# AccShelf.net
KiCad netlist of a schematic drawn in Altium Designer
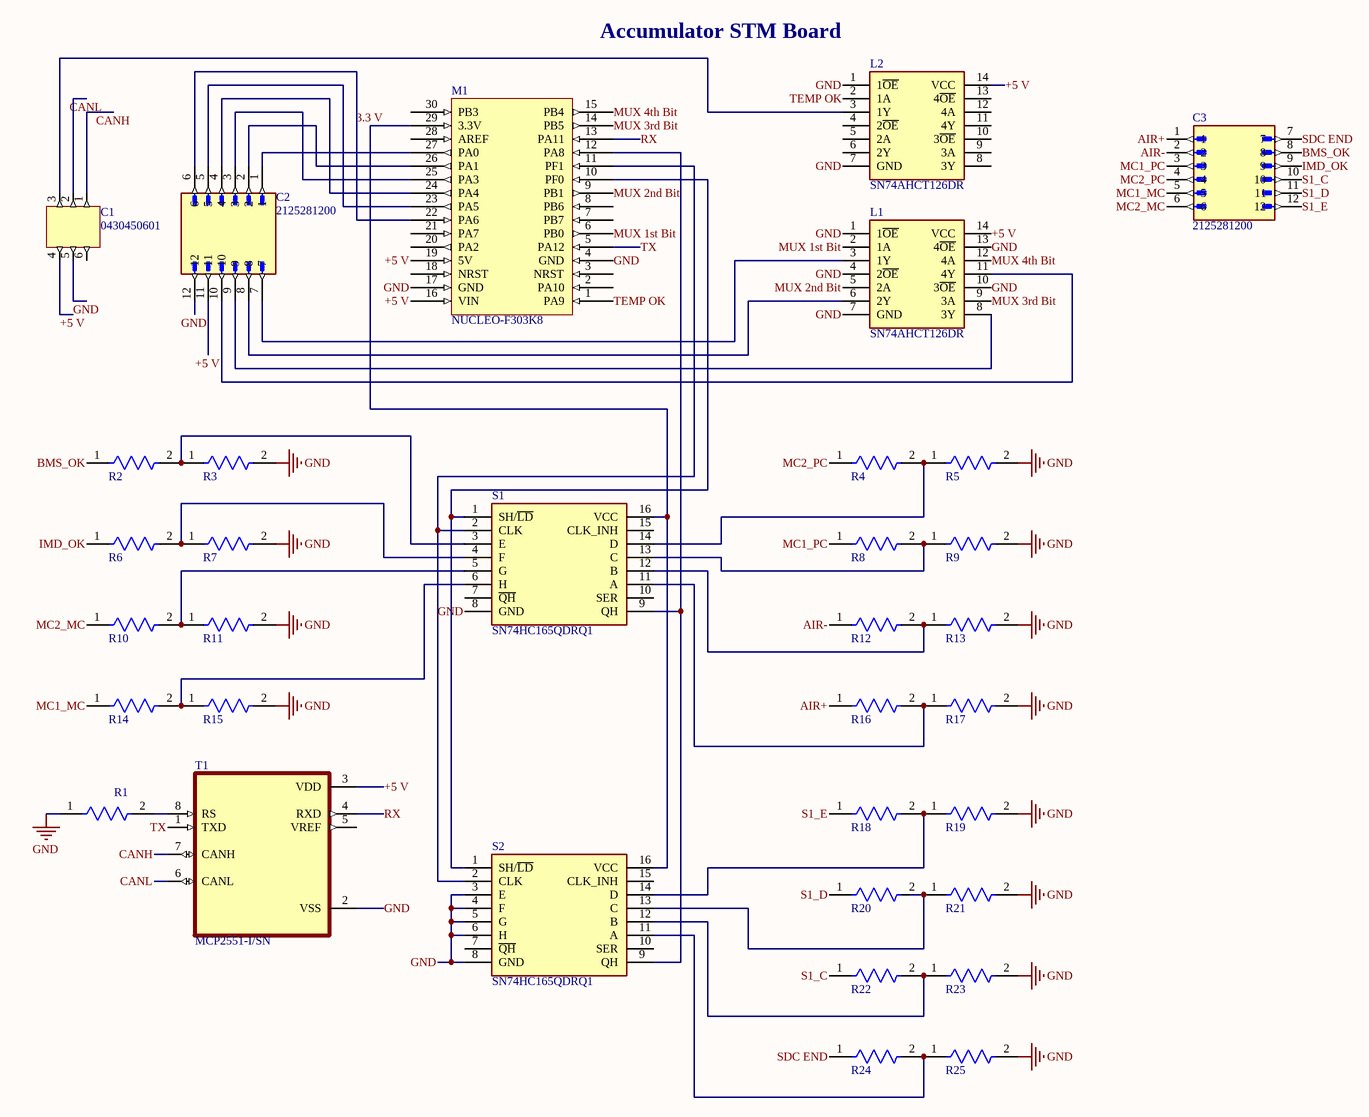
[diagram p0: AccShelf.SchDoc]

(export (version "E")
  (design (tool "Eeschema 10.0.6"))
  (components
    (comp (ref "C1")
      (value "0430450601")
      (footprint "6 Pin Dual Connector")
      (description "Rectangular Power Connector, 6 Contact(s), Male, Solder Terminal, Receptacle")
      (fields
        (field (name "MANUFACTURER") "Sullins")
        (field (name "MANUFACTURER PART NUMBER") "PPPC032LJBN-RC")
      )
      (libsource (lib "AccShelf") (part "0430450601"))
    )
    (comp (ref "C2")
      (value "2125281200")
      (footprint "12 Pin Dual Inline Connector")
      (description "Conn Micro-Fit Power HDR 12 POS 3mm Solder RA Through Hole 12 Terminal Single Port Tray")
      (fields (field (name "MF") "{'manufacturer': u'Molex'}") (field (name "MANUFACTURER") "Molex"))
      (libsource (lib "AccShelf") (part "2125281200"))
    )
    (comp (ref "C3")
      (value "2125281200")
      (footprint "12 Pin Dual Inline Connector")
      (description "Conn Micro-Fit Power HDR 12 POS 3mm Solder RA Through Hole 12 Terminal Single Port Tray")
      (fields (field (name "MF") "{'manufacturer': u'Molex'}") (field (name "MANUFACTURER") "Molex"))
      (libsource (lib "") (part "2125281200_1"))
    )
    (comp (ref "L1")
      (value "SN74AHCT126DR")
      (footprint "Level Shifter")
      (description "Bus Driver, AHCT/VHCT/VT Series, 4-Func, 1-Bit, True Output, CMOS, PDSO14")
      (fields
        (field (name "MANUFACTURER_PART_NUMBER") "74AHCT125S14-13")
        (field (name "MOUSER PART NUMBER") "621-74AHCT125S14-13")
      )
      (libsource (lib "AccShelf") (part "SN74AHCT126DR"))
    )
    (comp (ref "L2")
      (value "SN74AHCT126DR")
      (footprint "Level Shifter")
      (description "Bus Driver, AHCT/VHCT/VT Series, 4-Func, 1-Bit, True Output, CMOS, PDSO14")
      (fields
        (field (name "MANUFACTURER_PART_NUMBER") "74AHCT125S14-13")
        (field (name "MOUSER PART NUMBER") "621-74AHCT125S14-13")
      )
      (libsource (lib "AccShelf") (part "SN74AHCT126DR"))
    )
    (comp (ref "M1")
      (value "NUCLEO-F303K8")
      (footprint "STM Footprint")
      (description "Boards/Accessories")
      (fields (field (name "MANUFACTURER") "STMicroelectronics"))
      (libsource (lib "AccShelf") (part "NUCLEO-F303K8"))
    )
    (comp (ref "R1")
      (value "CRCW080510K0FKEA")
      (footprint "FP-CRCW0805-e3-IPC_A")
      (description "RES Thick Film, 10kΩ, 1%, 0.125W, 100ppm/°C, 0805")
      (fields (field (name "TOLERANCE") "1%") (field (name "MANUFACTURER") "Vishay"))
      (libsource (lib "Altium Content Vault") (part "1029c3af85768c4190bb7ad29bc67b5"))
    )
    (comp (ref "R2")
      (value "CRCW0805270KFKEA")
      (footprint "FP-CRCW0805-e3-IPC_A")
      (description "RES Thick Film, 270kΩ, 1%, 0.125W, 100ppm/°C, 0805")
      (fields (field (name "TOLERANCE") "1%"))
      (libsource (lib "Altium Content Vault") (part "1029c3af85768c4190bb7ad29bc67b5"))
    )
    (comp (ref "R3")
      (value "CRCW0805100KFKEA")
      (footprint "FP-CRCW0805-e3-MFG")
      (description "RES Thick Film, 100kΩ, 1%, 0.125W, 100ppm/°C, 0805")
      (fields (field (name "TOLERANCE") "1%"))
      (libsource (lib "Altium Content Vault") (part "1029c3af85768c4190bb7ad29bc67b5"))
    )
    (comp (ref "R4")
      (value "CRCW0805270KFKEA")
      (footprint "FP-CRCW0805-e3-IPC_A")
      (description "RES Thick Film, 270kΩ, 1%, 0.125W, 100ppm/°C, 0805")
      (fields (field (name "TOLERANCE") "1%"))
      (libsource (lib "Altium Content Vault") (part "1029c3af85768c4190bb7ad29bc67b5"))
    )
    (comp (ref "R5")
      (value "CRCW0805100KFKEA")
      (footprint "FP-CRCW0805-e3-MFG")
      (description "RES Thick Film, 100kΩ, 1%, 0.125W, 100ppm/°C, 0805")
      (fields (field (name "TOLERANCE") "1%"))
      (libsource (lib "Altium Content Vault") (part "1029c3af85768c4190bb7ad29bc67b5"))
    )
    (comp (ref "R6")
      (value "CRCW0805270KFKEA")
      (footprint "FP-CRCW0805-e3-IPC_A")
      (description "RES Thick Film, 270kΩ, 1%, 0.125W, 100ppm/°C, 0805")
      (fields (field (name "TOLERANCE") "1%"))
      (libsource (lib "Altium Content Vault") (part "1029c3af85768c4190bb7ad29bc67b5"))
    )
    (comp (ref "R7")
      (value "CRCW0805100KFKEA")
      (footprint "FP-CRCW0805-e3-MFG")
      (description "RES Thick Film, 100kΩ, 1%, 0.125W, 100ppm/°C, 0805")
      (fields (field (name "TOLERANCE") "1%"))
      (libsource (lib "Altium Content Vault") (part "1029c3af85768c4190bb7ad29bc67b5"))
    )
    (comp (ref "R8")
      (value "CRCW0805270KFKEA")
      (footprint "FP-CRCW0805-e3-IPC_A")
      (description "RES Thick Film, 270kΩ, 1%, 0.125W, 100ppm/°C, 0805")
      (fields (field (name "TOLERANCE") "1%"))
      (libsource (lib "Altium Content Vault") (part "1029c3af85768c4190bb7ad29bc67b5"))
    )
    (comp (ref "R9")
      (value "CRCW0805100KFKEA")
      (footprint "FP-CRCW0805-e3-MFG")
      (description "RES Thick Film, 100kΩ, 1%, 0.125W, 100ppm/°C, 0805")
      (fields (field (name "TOLERANCE") "1%"))
      (libsource (lib "Altium Content Vault") (part "1029c3af85768c4190bb7ad29bc67b5"))
    )
    (comp (ref "R10")
      (value "CRCW0805270KFKEA")
      (footprint "FP-CRCW0805-e3-IPC_A")
      (description "RES Thick Film, 270kΩ, 1%, 0.125W, 100ppm/°C, 0805")
      (fields (field (name "TOLERANCE") "1%"))
      (libsource (lib "Altium Content Vault") (part "1029c3af85768c4190bb7ad29bc67b5"))
    )
    (comp (ref "R11")
      (value "CRCW0805100KFKEA")
      (footprint "FP-CRCW0805-e3-MFG")
      (description "RES Thick Film, 100kΩ, 1%, 0.125W, 100ppm/°C, 0805")
      (fields (field (name "TOLERANCE") "1%"))
      (libsource (lib "Altium Content Vault") (part "1029c3af85768c4190bb7ad29bc67b5"))
    )
    (comp (ref "R12")
      (value "CRCW0805270KFKEA")
      (footprint "FP-CRCW0805-e3-IPC_A")
      (description "RES Thick Film, 270kΩ, 1%, 0.125W, 100ppm/°C, 0805")
      (fields (field (name "TOLERANCE") "1%"))
      (libsource (lib "Altium Content Vault") (part "1029c3af85768c4190bb7ad29bc67b5"))
    )
    (comp (ref "R13")
      (value "CRCW0805100KFKEA")
      (footprint "FP-CRCW0805-e3-MFG")
      (description "RES Thick Film, 100kΩ, 1%, 0.125W, 100ppm/°C, 0805")
      (fields (field (name "TOLERANCE") "1%"))
      (libsource (lib "Altium Content Vault") (part "1029c3af85768c4190bb7ad29bc67b5"))
    )
    (comp (ref "R14")
      (value "CRCW0805270KFKEA")
      (footprint "FP-CRCW0805-e3-IPC_A")
      (description "RES Thick Film, 270kΩ, 1%, 0.125W, 100ppm/°C, 0805")
      (fields (field (name "TOLERANCE") "1%"))
      (libsource (lib "Altium Content Vault") (part "1029c3af85768c4190bb7ad29bc67b5"))
    )
    (comp (ref "R15")
      (value "CRCW0805100KFKEA")
      (footprint "FP-CRCW0805-e3-MFG")
      (description "RES Thick Film, 100kΩ, 1%, 0.125W, 100ppm/°C, 0805")
      (fields (field (name "TOLERANCE") "1%"))
      (libsource (lib "Altium Content Vault") (part "1029c3af85768c4190bb7ad29bc67b5"))
    )
    (comp (ref "R16")
      (value "CRCW0805270KFKEA")
      (footprint "FP-CRCW0805-e3-IPC_A")
      (description "RES Thick Film, 270kΩ, 1%, 0.125W, 100ppm/°C, 0805")
      (fields (field (name "TOLERANCE") "1%"))
      (libsource (lib "Altium Content Vault") (part "1029c3af85768c4190bb7ad29bc67b5"))
    )
    (comp (ref "R17")
      (value "CRCW0805100KFKEA")
      (footprint "FP-CRCW0805-e3-MFG")
      (description "RES Thick Film, 100kΩ, 1%, 0.125W, 100ppm/°C, 0805")
      (fields (field (name "TOLERANCE") "1%"))
      (libsource (lib "Altium Content Vault") (part "1029c3af85768c4190bb7ad29bc67b5"))
    )
    (comp (ref "R18")
      (value "CRCW0805270KFKEA")
      (footprint "FP-CRCW0805-e3-IPC_A")
      (description "RES Thick Film, 270kΩ, 1%, 0.125W, 100ppm/°C, 0805")
      (fields (field (name "TOLERANCE") "1%"))
      (libsource (lib "Altium Content Vault") (part "1029c3af85768c4190bb7ad29bc67b5"))
    )
    (comp (ref "R19")
      (value "CRCW0805100KFKEA")
      (footprint "FP-CRCW0805-e3-MFG")
      (description "RES Thick Film, 100kΩ, 1%, 0.125W, 100ppm/°C, 0805")
      (fields (field (name "TOLERANCE") "1%"))
      (libsource (lib "Altium Content Vault") (part "1029c3af85768c4190bb7ad29bc67b5"))
    )
    (comp (ref "R20")
      (value "CRCW0805270KFKEA")
      (footprint "FP-CRCW0805-e3-IPC_A")
      (description "RES Thick Film, 270kΩ, 1%, 0.125W, 100ppm/°C, 0805")
      (fields (field (name "TOLERANCE") "1%"))
      (libsource (lib "Altium Content Vault") (part "1029c3af85768c4190bb7ad29bc67b5"))
    )
    (comp (ref "R21")
      (value "CRCW0805100KFKEA")
      (footprint "FP-CRCW0805-e3-MFG")
      (description "RES Thick Film, 100kΩ, 1%, 0.125W, 100ppm/°C, 0805")
      (fields (field (name "TOLERANCE") "1%"))
      (libsource (lib "Altium Content Vault") (part "1029c3af85768c4190bb7ad29bc67b5"))
    )
    (comp (ref "R22")
      (value "CRCW0805270KFKEA")
      (footprint "FP-CRCW0805-e3-IPC_A")
      (description "RES Thick Film, 270kΩ, 1%, 0.125W, 100ppm/°C, 0805")
      (fields (field (name "TOLERANCE") "1%"))
      (libsource (lib "Altium Content Vault") (part "1029c3af85768c4190bb7ad29bc67b5"))
    )
    (comp (ref "R23")
      (value "CRCW0805100KFKEA")
      (footprint "FP-CRCW0805-e3-MFG")
      (description "RES Thick Film, 100kΩ, 1%, 0.125W, 100ppm/°C, 0805")
      (fields (field (name "TOLERANCE") "1%"))
      (libsource (lib "Altium Content Vault") (part "1029c3af85768c4190bb7ad29bc67b5"))
    )
    (comp (ref "R24")
      (value "CRCW0805270KFKEA")
      (footprint "FP-CRCW0805-e3-IPC_A")
      (description "RES Thick Film, 270kΩ, 1%, 0.125W, 100ppm/°C, 0805")
      (fields (field (name "TOLERANCE") "1%"))
      (libsource (lib "Altium Content Vault") (part "1029c3af85768c4190bb7ad29bc67b5"))
    )
    (comp (ref "R25")
      (value "CRCW0805100KFKEA")
      (footprint "FP-CRCW0805-e3-MFG")
      (description "RES Thick Film, 100kΩ, 1%, 0.125W, 100ppm/°C, 0805")
      (fields (field (name "TOLERANCE") "1%"))
      (libsource (lib "Altium Content Vault") (part "1029c3af85768c4190bb7ad29bc67b5"))
    )
    (comp (ref "S1")
      (value "SN74HC165QDRQ1")
      (footprint "Shift Register")
      (description "Parallel In Serial Out, HC Series, 8-Bit, Right Direction, Complementary Output, CMOS, PDSO16")
      (fields
        (field (name "MOUSER PART NUMBER") "595-SN74HC165QDRQ1")
        (field (name "MANUFACTURER") "Texas Instruments")
      )
      (libsource (lib "AccShelf") (part "SN74HC165QDRQ1"))
    )
    (comp (ref "S2")
      (value "SN74HC165QDRQ1")
      (footprint "Shift Register")
      (description "Parallel In Serial Out, HC Series, 8-Bit, Right Direction, Complementary Output, CMOS, PDSO16")
      (fields
        (field (name "MOUSER PART NUMBER") "595-SN74HC165QDRQ1")
        (field (name "MANUFACTURER") "Texas Instruments")
      )
      (libsource (lib "AccShelf") (part "SN74HC165QDRQ1"))
    )
    (comp (ref "T1")
      (value "MCP2551-I/SN")
      (footprint "CAN Transceiver")
      (description "CAN Transceiver, 1-Trnsvr, PDSO8")
      (fields (field (name "MANUFACTURER") "Microchip"))
      (libsource (lib "AccShelf") (part "MCP2551-I/SN"))
    )
  )
  (nets
    (net (code "1") (name "/+5 V") (class "Default")
      (node (ref "C1") (pin "4") (pintype "output"))
      (node (ref "C2") (pin "11") (pinfunction "11_11") (pintype "output"))
      (node (ref "L1") (pin "14") (pinfunction "VCC_14") (pintype "power_in"))
      (node (ref "L2") (pin "14") (pinfunction "VCC_14") (pintype "power_in"))
      (node (ref "M1") (pin "16") (pinfunction "VIN_16") (pintype "input"))
      (node (ref "M1") (pin "19") (pinfunction "5V_19") (pintype "input"))
      (node (ref "T1") (pin "3") (pinfunction "VDD_3") (pintype "power_in"))
    )
    (net (code "2") (name "/3.3 V") (class "Default")
      (node (ref "M1") (pin "29") (pinfunction "3.3V_29") (pintype "input"))
      (node (ref "S1") (pin "16") (pinfunction "VCC_16") (pintype "passive"))
      (node (ref "S2") (pin "16") (pinfunction "VCC_16") (pintype "passive"))
    )
    (net (code "3") (name "/AIR+") (class "Default")
      (node (ref "C3") (pin "1") (pinfunction "1_1") (pintype "output"))
      (node (ref "R16") (pin "1") (pinfunction "1_1") (pintype "passive"))
    )
    (net (code "4") (name "/AIR-") (class "Default")
      (node (ref "C3") (pin "2") (pinfunction "2_2") (pintype "output"))
      (node (ref "R12") (pin "1") (pinfunction "1_1") (pintype "passive"))
    )
    (net (code "5") (name "/BMS_OK") (class "Default")
      (node (ref "C3") (pin "8") (pinfunction "8_8") (pintype "output"))
      (node (ref "R2") (pin "1") (pinfunction "1_1") (pintype "passive"))
    )
    (net (code "6") (name "/CANH") (class "Default")
      (node (ref "C1") (pin "1") (pintype "output"))
      (node (ref "T1") (pin "7") (pinfunction "CANH_7") (pintype "bidirectional"))
    )
    (net (code "7") (name "/CANL") (class "Default")
      (node (ref "C1") (pin "2") (pintype "output"))
      (node (ref "T1") (pin "6") (pinfunction "CANL_6") (pintype "bidirectional"))
    )
    (net (code "8") (name "/IMD_OK") (class "Default")
      (node (ref "C3") (pin "9") (pinfunction "9_9") (pintype "output"))
      (node (ref "R6") (pin "1") (pinfunction "1_1") (pintype "passive"))
    )
    (net (code "9") (name "/MC1_MC") (class "Default")
      (node (ref "C3") (pin "5") (pinfunction "5_5") (pintype "output"))
      (node (ref "R14") (pin "1") (pinfunction "1_1") (pintype "passive"))
    )
    (net (code "10") (name "/MC1_PC") (class "Default")
      (node (ref "C3") (pin "3") (pinfunction "3_3") (pintype "output"))
      (node (ref "R8") (pin "1") (pinfunction "1_1") (pintype "passive"))
    )
    (net (code "11") (name "/MC2_MC") (class "Default")
      (node (ref "C3") (pin "6") (pinfunction "6_6") (pintype "output"))
      (node (ref "R10") (pin "1") (pinfunction "1_1") (pintype "passive"))
    )
    (net (code "12") (name "/MC2_PC") (class "Default")
      (node (ref "C3") (pin "4") (pinfunction "4_4") (pintype "output"))
      (node (ref "R4") (pin "1") (pinfunction "1_1") (pintype "passive"))
    )
    (net (code "13") (name "/MUX 1st Bit") (class "Default")
      (node (ref "L1") (pin "2") (pinfunction "1A_2") (pintype "passive"))
      (node (ref "M1") (pin "6") (pinfunction "PB0_6") (pintype "output"))
    )
    (net (code "14") (name "/MUX 2nd Bit") (class "Default")
      (node (ref "L1") (pin "5") (pinfunction "2A_5") (pintype "passive"))
      (node (ref "M1") (pin "9") (pinfunction "PB1_9") (pintype "output"))
    )
    (net (code "15") (name "/MUX 3rd Bit") (class "Default")
      (node (ref "L1") (pin "9") (pinfunction "3A_9") (pintype "passive"))
      (node (ref "M1") (pin "14") (pinfunction "PB5_14") (pintype "output"))
    )
    (net (code "16") (name "/MUX 4th Bit") (class "Default")
      (node (ref "L1") (pin "12") (pinfunction "4A_12") (pintype "passive"))
      (node (ref "M1") (pin "15") (pinfunction "PB4_15") (pintype "output"))
    )
    (net (code "17") (name "/RX") (class "Default")
      (node (ref "M1") (pin "13") (pinfunction "PA11_13") (pintype "input"))
      (node (ref "T1") (pin "4") (pinfunction "RXD_4") (pintype "output"))
    )
    (net (code "18") (name "/S1_C") (class "Default")
      (node (ref "C3") (pin "10") (pinfunction "10_10") (pintype "output"))
      (node (ref "R22") (pin "1") (pinfunction "1_1") (pintype "passive"))
    )
    (net (code "19") (name "/S1_D") (class "Default")
      (node (ref "C3") (pin "11") (pinfunction "11_11") (pintype "output"))
      (node (ref "R20") (pin "1") (pinfunction "1_1") (pintype "passive"))
    )
    (net (code "20") (name "/S1_E") (class "Default")
      (node (ref "C3") (pin "12") (pinfunction "12_12") (pintype "output"))
      (node (ref "R18") (pin "1") (pinfunction "1_1") (pintype "passive"))
    )
    (net (code "21") (name "/SDC END") (class "Default")
      (node (ref "C3") (pin "7") (pinfunction "7_7") (pintype "output"))
      (node (ref "R24") (pin "1") (pinfunction "1_1") (pintype "passive"))
    )
    (net (code "22") (name "/TEMP OK") (class "Default")
      (node (ref "L2") (pin "2") (pinfunction "1A_2") (pintype "passive"))
      (node (ref "M1") (pin "1") (pinfunction "PA9_1") (pintype "input"))
    )
    (net (code "23") (name "/TX") (class "Default")
      (node (ref "M1") (pin "5") (pinfunction "PA12_5") (pintype "input"))
      (node (ref "T1") (pin "1") (pinfunction "TXD_1") (pintype "input"))
    )
    (net (code "24") (name "GND") (class "Default")
      (node (ref "C1") (pin "5") (pintype "output"))
      (node (ref "C2") (pin "12") (pinfunction "12_12") (pintype "output"))
      (node (ref "L1") (pin "1") (pinfunction "1~{OE}_1") (pintype "passive"))
      (node (ref "L1") (pin "10") (pinfunction "3~{OE}_10") (pintype "passive"))
      (node (ref "L1") (pin "13") (pinfunction "4~{OE}_13") (pintype "passive"))
      (node (ref "L1") (pin "4") (pinfunction "2~{OE}_4") (pintype "passive"))
      (node (ref "L1") (pin "7") (pinfunction "GND_7") (pintype "passive"))
      (node (ref "L2") (pin "1") (pinfunction "1~{OE}_1") (pintype "passive"))
      (node (ref "L2") (pin "7") (pinfunction "GND_7") (pintype "passive"))
      (node (ref "M1") (pin "17") (pinfunction "GND_17") (pintype "input"))
      (node (ref "M1") (pin "4") (pinfunction "GND_4") (pintype "input"))
      (node (ref "R1") (pin "1") (pinfunction "1_1") (pintype "passive"))
      (node (ref "R11") (pin "2") (pinfunction "2_2") (pintype "passive"))
      (node (ref "R13") (pin "2") (pinfunction "2_2") (pintype "passive"))
      (node (ref "R15") (pin "2") (pinfunction "2_2") (pintype "passive"))
      (node (ref "R17") (pin "2") (pinfunction "2_2") (pintype "passive"))
      (node (ref "R19") (pin "2") (pinfunction "2_2") (pintype "passive"))
      (node (ref "R21") (pin "2") (pinfunction "2_2") (pintype "passive"))
      (node (ref "R23") (pin "2") (pinfunction "2_2") (pintype "passive"))
      (node (ref "R25") (pin "2") (pinfunction "2_2") (pintype "passive"))
      (node (ref "R3") (pin "2") (pinfunction "2_2") (pintype "passive"))
      (node (ref "R5") (pin "2") (pinfunction "2_2") (pintype "passive"))
      (node (ref "R7") (pin "2") (pinfunction "2_2") (pintype "passive"))
      (node (ref "R9") (pin "2") (pinfunction "2_2") (pintype "passive"))
      (node (ref "S1") (pin "8") (pinfunction "GND_8") (pintype "passive"))
      (node (ref "S2") (pin "3") (pinfunction "E_3") (pintype "passive"))
      (node (ref "S2") (pin "4") (pinfunction "F_4") (pintype "passive"))
      (node (ref "S2") (pin "5") (pinfunction "G_5") (pintype "passive"))
      (node (ref "S2") (pin "6") (pinfunction "H_6") (pintype "passive"))
      (node (ref "S2") (pin "8") (pinfunction "GND_8") (pintype "passive"))
      (node (ref "T1") (pin "2") (pinfunction "VSS_2") (pintype "power_in"))
    )
    (net (code "25") (name "Net-(L1-1Y)") (class "Default")
      (node (ref "C2") (pin "7") (pinfunction "7_7") (pintype "output"))
      (node (ref "L1") (pin "3") (pinfunction "1Y_3") (pintype "passive"))
    )
    (net (code "26") (name "Net-(L1-2Y)") (class "Default")
      (node (ref "C2") (pin "8") (pinfunction "8_8") (pintype "output"))
      (node (ref "L1") (pin "6") (pinfunction "2Y_6") (pintype "passive"))
    )
    (net (code "27") (name "Net-(L1-3Y)") (class "Default")
      (node (ref "C2") (pin "9") (pinfunction "9_9") (pintype "output"))
      (node (ref "L1") (pin "8") (pinfunction "3Y_8") (pintype "passive"))
    )
    (net (code "28") (name "Net-(L1-4Y)") (class "Default")
      (node (ref "C2") (pin "10") (pinfunction "10_10") (pintype "output"))
      (node (ref "L1") (pin "11") (pinfunction "4Y_11") (pintype "passive"))
    )
    (net (code "29") (name "Net-(L2-1Y)") (class "Default")
      (node (ref "C1") (pin "3") (pintype "output"))
      (node (ref "L2") (pin "3") (pinfunction "1Y_3") (pintype "passive"))
    )
    (net (code "30") (name "Net-(M1-PA0)") (class "Default")
      (node (ref "C2") (pin "1") (pinfunction "1_1") (pintype "output"))
      (node (ref "M1") (pin "27") (pinfunction "PA0_27") (pintype "output"))
    )
    (net (code "31") (name "Net-(M1-PA1)") (class "Default")
      (node (ref "C2") (pin "2") (pinfunction "2_2") (pintype "output"))
      (node (ref "M1") (pin "26") (pinfunction "PA1_26") (pintype "output"))
    )
    (net (code "32") (name "Net-(M1-PA3)") (class "Default")
      (node (ref "C2") (pin "3") (pinfunction "3_3") (pintype "output"))
      (node (ref "M1") (pin "25") (pinfunction "PA3_25") (pintype "output"))
    )
    (net (code "33") (name "Net-(M1-PA4)") (class "Default")
      (node (ref "C2") (pin "4") (pinfunction "4_4") (pintype "output"))
      (node (ref "M1") (pin "24") (pinfunction "PA4_24") (pintype "output"))
    )
    (net (code "34") (name "Net-(M1-PA5)") (class "Default")
      (node (ref "C2") (pin "5") (pinfunction "5_5") (pintype "output"))
      (node (ref "M1") (pin "23") (pinfunction "PA5_23") (pintype "output"))
    )
    (net (code "35") (name "Net-(M1-PA6)") (class "Default")
      (node (ref "C2") (pin "6") (pinfunction "6_6") (pintype "output"))
      (node (ref "M1") (pin "22") (pinfunction "PA6_22") (pintype "input"))
    )
    (net (code "36") (name "Net-(M1-PA8)") (class "Default")
      (node (ref "M1") (pin "12") (pinfunction "PA8_12") (pintype "input"))
      (node (ref "S1") (pin "9") (pinfunction "QH_9") (pintype "passive"))
      (node (ref "S2") (pin "9") (pinfunction "QH_9") (pintype "passive"))
    )
    (net (code "37") (name "Net-(M1-PF0)") (class "Default")
      (node (ref "M1") (pin "10") (pinfunction "PF0_10") (pintype "input"))
      (node (ref "S1") (pin "1") (pinfunction "SH/~{LD}_1") (pintype "passive"))
      (node (ref "S2") (pin "1") (pinfunction "SH/~{LD}_1") (pintype "passive"))
    )
    (net (code "38") (name "Net-(M1-PF1)") (class "Default")
      (node (ref "M1") (pin "11") (pinfunction "PF1_11") (pintype "input"))
      (node (ref "S1") (pin "2") (pinfunction "CLK_2") (pintype "passive"))
      (node (ref "S2") (pin "2") (pinfunction "CLK_2") (pintype "passive"))
    )
    (net (code "39") (name "Net-(S1-A)") (class "Default")
      (node (ref "R16") (pin "2") (pinfunction "2_2") (pintype "passive"))
      (node (ref "R17") (pin "1") (pinfunction "1_1") (pintype "passive"))
      (node (ref "S1") (pin "11") (pinfunction "A_11") (pintype "passive"))
    )
    (net (code "40") (name "Net-(S1-B)") (class "Default")
      (node (ref "R12") (pin "2") (pinfunction "2_2") (pintype "passive"))
      (node (ref "R13") (pin "1") (pinfunction "1_1") (pintype "passive"))
      (node (ref "S1") (pin "12") (pinfunction "B_12") (pintype "passive"))
    )
    (net (code "41") (name "Net-(S1-C)") (class "Default")
      (node (ref "R8") (pin "2") (pinfunction "2_2") (pintype "passive"))
      (node (ref "R9") (pin "1") (pinfunction "1_1") (pintype "passive"))
      (node (ref "S1") (pin "13") (pinfunction "C_13") (pintype "passive"))
    )
    (net (code "42") (name "Net-(S1-D)") (class "Default")
      (node (ref "R4") (pin "2") (pinfunction "2_2") (pintype "passive"))
      (node (ref "R5") (pin "1") (pinfunction "1_1") (pintype "passive"))
      (node (ref "S1") (pin "14") (pinfunction "D_14") (pintype "passive"))
    )
    (net (code "43") (name "Net-(S1-E)") (class "Default")
      (node (ref "R2") (pin "2") (pinfunction "2_2") (pintype "passive"))
      (node (ref "R3") (pin "1") (pinfunction "1_1") (pintype "passive"))
      (node (ref "S1") (pin "3") (pinfunction "E_3") (pintype "passive"))
    )
    (net (code "44") (name "Net-(S1-F)") (class "Default")
      (node (ref "R6") (pin "2") (pinfunction "2_2") (pintype "passive"))
      (node (ref "R7") (pin "1") (pinfunction "1_1") (pintype "passive"))
      (node (ref "S1") (pin "4") (pinfunction "F_4") (pintype "passive"))
    )
    (net (code "45") (name "Net-(S1-G)") (class "Default")
      (node (ref "R10") (pin "2") (pinfunction "2_2") (pintype "passive"))
      (node (ref "R11") (pin "1") (pinfunction "1_1") (pintype "passive"))
      (node (ref "S1") (pin "5") (pinfunction "G_5") (pintype "passive"))
    )
    (net (code "46") (name "Net-(S1-H)") (class "Default")
      (node (ref "R14") (pin "2") (pinfunction "2_2") (pintype "passive"))
      (node (ref "R15") (pin "1") (pinfunction "1_1") (pintype "passive"))
      (node (ref "S1") (pin "6") (pinfunction "H_6") (pintype "passive"))
    )
    (net (code "47") (name "Net-(S2-A)") (class "Default")
      (node (ref "R24") (pin "2") (pinfunction "2_2") (pintype "passive"))
      (node (ref "R25") (pin "1") (pinfunction "1_1") (pintype "passive"))
      (node (ref "S2") (pin "11") (pinfunction "A_11") (pintype "passive"))
    )
    (net (code "48") (name "Net-(S2-B)") (class "Default")
      (node (ref "R22") (pin "2") (pinfunction "2_2") (pintype "passive"))
      (node (ref "R23") (pin "1") (pinfunction "1_1") (pintype "passive"))
      (node (ref "S2") (pin "12") (pinfunction "B_12") (pintype "passive"))
    )
    (net (code "49") (name "Net-(S2-C)") (class "Default")
      (node (ref "R20") (pin "2") (pinfunction "2_2") (pintype "passive"))
      (node (ref "R21") (pin "1") (pinfunction "1_1") (pintype "passive"))
      (node (ref "S2") (pin "13") (pinfunction "C_13") (pintype "passive"))
    )
    (net (code "50") (name "Net-(S2-D)") (class "Default")
      (node (ref "R18") (pin "2") (pinfunction "2_2") (pintype "passive"))
      (node (ref "R19") (pin "1") (pinfunction "1_1") (pintype "passive"))
      (node (ref "S2") (pin "14") (pinfunction "D_14") (pintype "passive"))
    )
    (net (code "51") (name "Net-(T1-RS)") (class "Default")
      (node (ref "R1") (pin "2") (pinfunction "2_2") (pintype "passive"))
      (node (ref "T1") (pin "8") (pinfunction "RS_8") (pintype "input"))
    )
    (net (code "52") (name "unconnected-(C1-Pad6)") (class "Default")
      (node (ref "C1") (pin "6") (pintype "output"))
    )
    (net (code "53") (name "unconnected-(L2-2A-Pad5)") (class "Default")
      (node (ref "L2") (pin "5") (pinfunction "2A_5") (pintype "passive"))
    )
    (net (code "54") (name "unconnected-(L2-2Y-Pad6)") (class "Default")
      (node (ref "L2") (pin "6") (pinfunction "2Y_6") (pintype "passive"))
    )
    (net (code "55") (name "unconnected-(L2-2~{OE}-Pad4)") (class "Default")
      (node (ref "L2") (pin "4") (pinfunction "2~{OE}_4") (pintype "passive"))
    )
    (net (code "56") (name "unconnected-(L2-3A-Pad9)") (class "Default")
      (node (ref "L2") (pin "9") (pinfunction "3A_9") (pintype "passive"))
    )
    (net (code "57") (name "unconnected-(L2-3Y-Pad8)") (class "Default")
      (node (ref "L2") (pin "8") (pinfunction "3Y_8") (pintype "passive"))
    )
    (net (code "58") (name "unconnected-(L2-3~{OE}-Pad10)") (class "Default")
      (node (ref "L2") (pin "10") (pinfunction "3~{OE}_10") (pintype "passive"))
    )
    (net (code "59") (name "unconnected-(L2-4A-Pad12)") (class "Default")
      (node (ref "L2") (pin "12") (pinfunction "4A_12") (pintype "passive"))
    )
    (net (code "60") (name "unconnected-(L2-4Y-Pad11)") (class "Default")
      (node (ref "L2") (pin "11") (pinfunction "4Y_11") (pintype "passive"))
    )
    (net (code "61") (name "unconnected-(L2-4~{OE}-Pad13)") (class "Default")
      (node (ref "L2") (pin "13") (pinfunction "4~{OE}_13") (pintype "passive"))
    )
    (net (code "62") (name "unconnected-(M1-AREF-Pad28)") (class "Default")
      (node (ref "M1") (pin "28") (pinfunction "AREF_28") (pintype "input"))
    )
    (net (code "63") (name "unconnected-(M1-NRST-Pad3)") (class "Default")
      (node (ref "M1") (pin "3") (pinfunction "NRST_3") (pintype "input"))
    )
    (net (code "64") (name "unconnected-(M1-NRST-Pad18)") (class "Default")
      (node (ref "M1") (pin "18") (pinfunction "NRST_18") (pintype "input"))
    )
    (net (code "65") (name "unconnected-(M1-PA2-Pad20)") (class "Default")
      (node (ref "M1") (pin "20") (pinfunction "PA2_20") (pintype "output"))
    )
    (net (code "66") (name "unconnected-(M1-PA7-Pad21)") (class "Default")
      (node (ref "M1") (pin "21") (pinfunction "PA7_21") (pintype "input"))
    )
    (net (code "67") (name "unconnected-(M1-PA10-Pad2)") (class "Default")
      (node (ref "M1") (pin "2") (pinfunction "PA10_2") (pintype "input"))
    )
    (net (code "68") (name "unconnected-(M1-PB3-Pad30)") (class "Default")
      (node (ref "M1") (pin "30") (pinfunction "PB3_30") (pintype "input"))
    )
    (net (code "69") (name "unconnected-(M1-PB6-Pad8)") (class "Default")
      (node (ref "M1") (pin "8") (pinfunction "PB6_8") (pintype "input"))
    )
    (net (code "70") (name "unconnected-(M1-PB7-Pad7)") (class "Default")
      (node (ref "M1") (pin "7") (pinfunction "PB7_7") (pintype "input"))
    )
    (net (code "71") (name "unconnected-(S1-CLK_INH-Pad15)") (class "Default")
      (node (ref "S1") (pin "15") (pinfunction "CLK_INH_15") (pintype "passive"))
    )
    (net (code "72") (name "unconnected-(S1-SER-Pad10)") (class "Default")
      (node (ref "S1") (pin "10") (pinfunction "SER_10") (pintype "passive"))
    )
    (net (code "73") (name "unconnected-(S1-~{QH}-Pad7)") (class "Default")
      (node (ref "S1") (pin "7") (pinfunction "~{QH}_7") (pintype "passive"))
    )
    (net (code "74") (name "unconnected-(S2-CLK_INH-Pad15)") (class "Default")
      (node (ref "S2") (pin "15") (pinfunction "CLK_INH_15") (pintype "passive"))
    )
    (net (code "75") (name "unconnected-(S2-SER-Pad10)") (class "Default")
      (node (ref "S2") (pin "10") (pinfunction "SER_10") (pintype "passive"))
    )
    (net (code "76") (name "unconnected-(S2-~{QH}-Pad7)") (class "Default")
      (node (ref "S2") (pin "7") (pinfunction "~{QH}_7") (pintype "passive"))
    )
    (net (code "77") (name "unconnected-(T1-VREF-Pad5)") (class "Default")
      (node (ref "T1") (pin "5") (pinfunction "VREF_5") (pintype "output"))
    )
  )
)
